# MF_badge_2021_rev_C.net
KiCad netlist of a schematic drawn in EAGLE
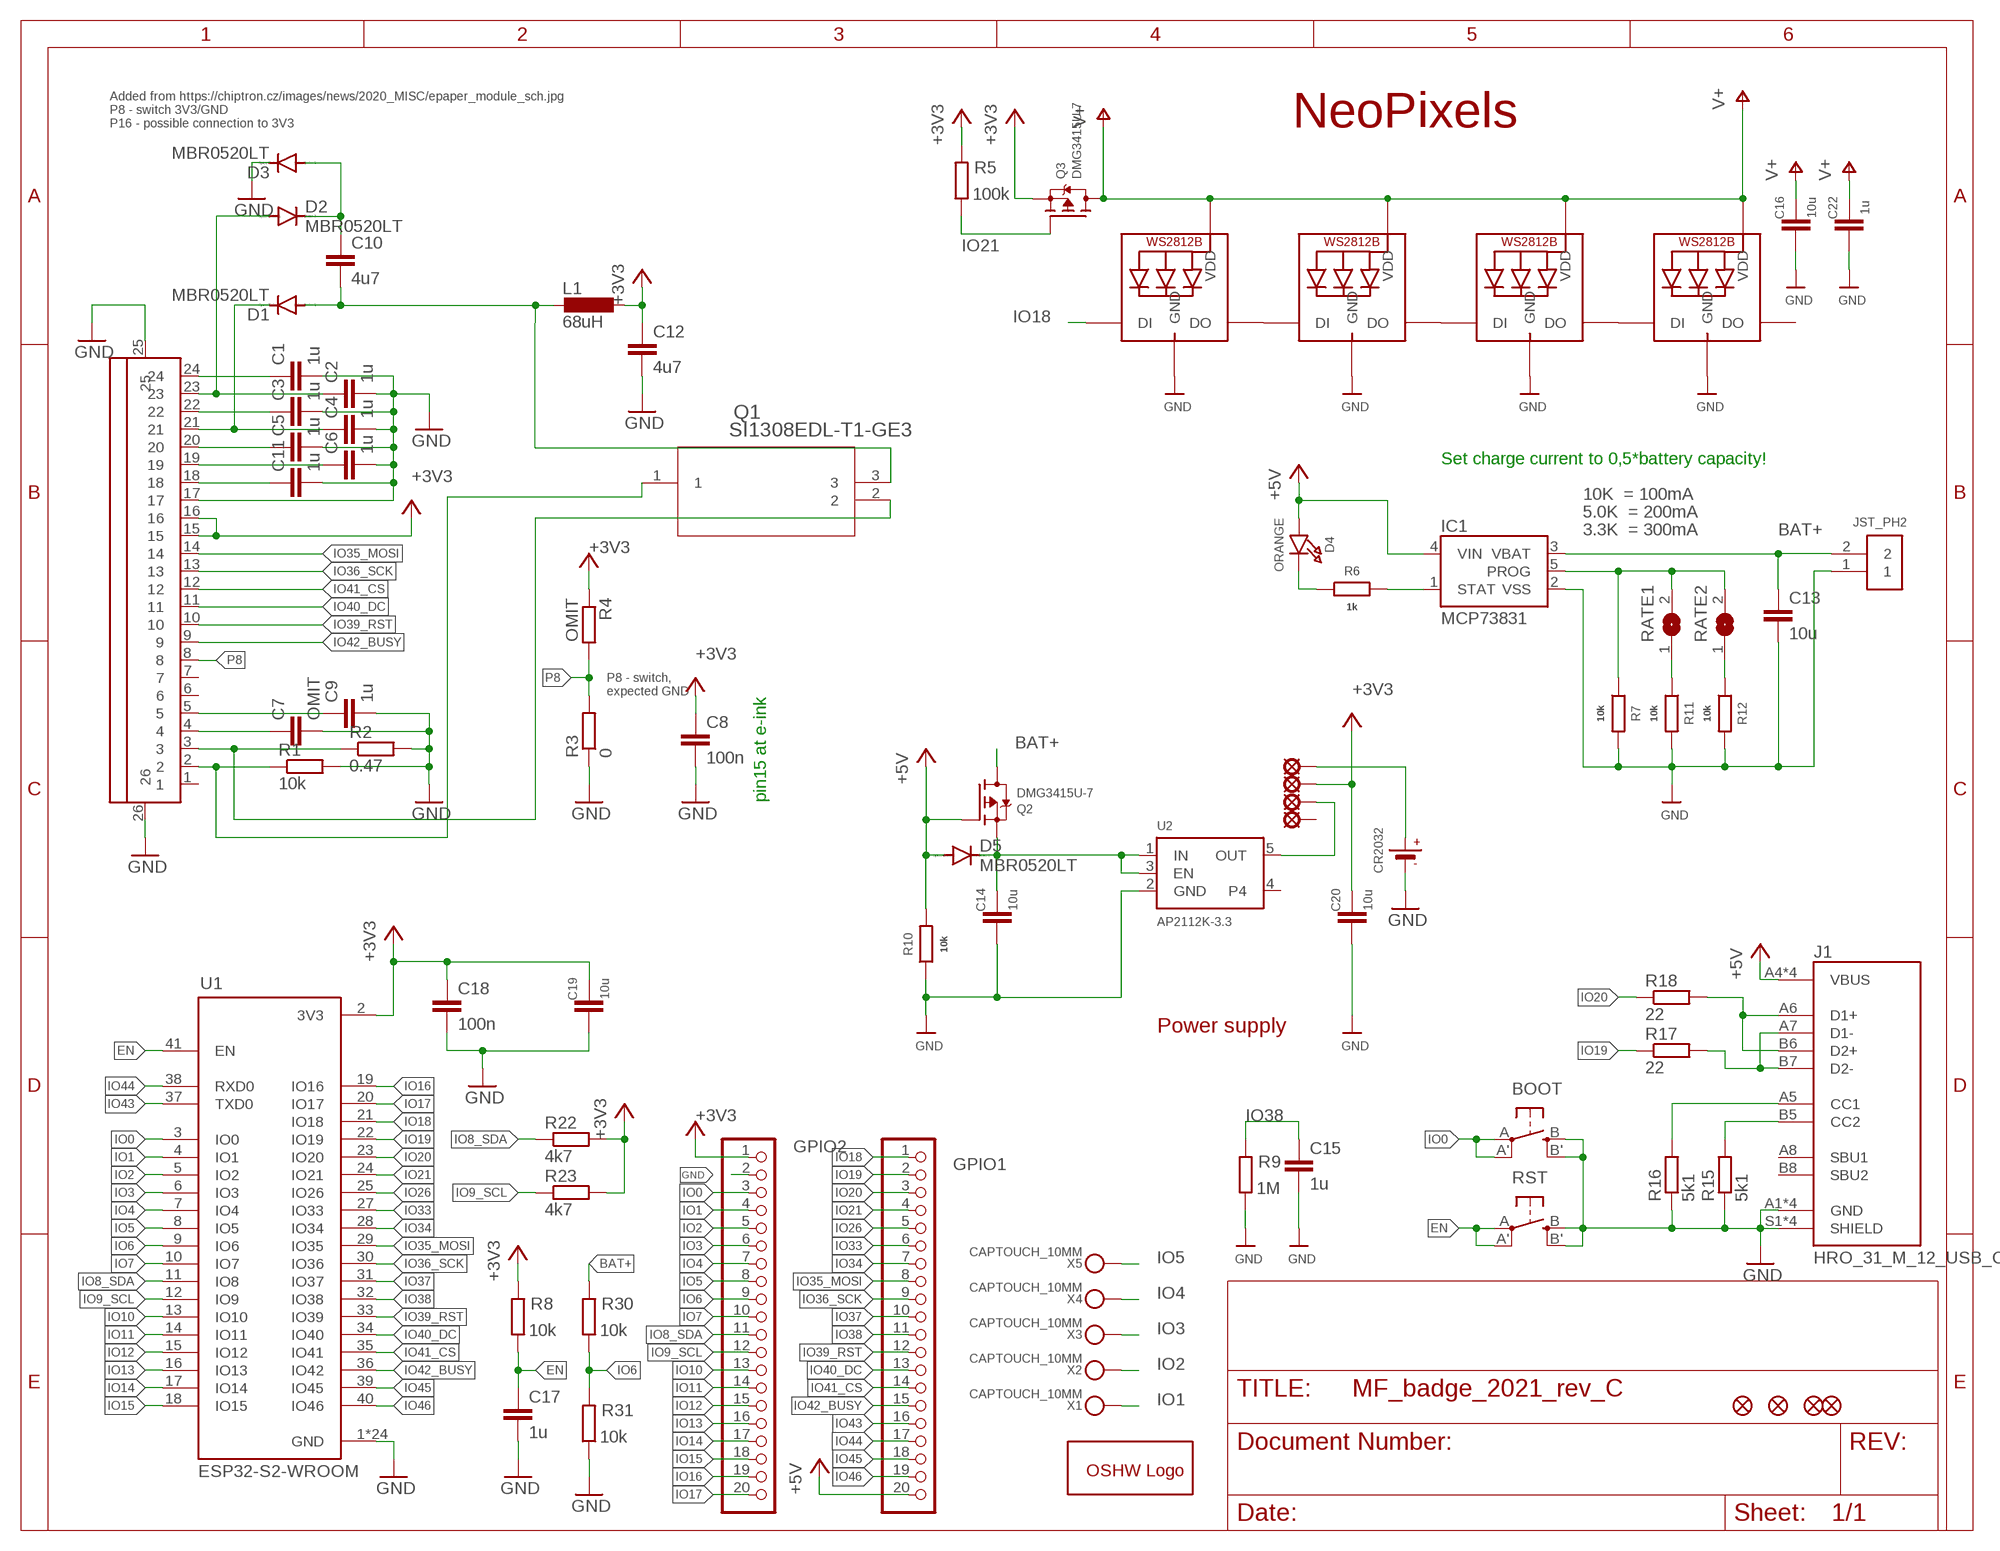
[diagram p0: schematic, sheet 1]

(export (version "E")
  (design (tool "Eeschema 10.0.6"))
  (components
    (comp (ref "BOOT")
      (value "BUTTON_KMR2_4.6X2.8")
      (footprint "eagle-import:BUTTON_KMR2_4.6X2.8")
      (libsource (lib "eagle-import") (part "BUTTON_KMR2_4.6X2.8"))
    )
    (comp (ref "C1")
      (value "1u")
      (footprint "eagle-import:C0805")
      (libsource (lib "eagle-import") (part "C-EUC0805"))
    )
    (comp (ref "C2")
      (value "1u")
      (footprint "eagle-import:C0805")
      (libsource (lib "eagle-import") (part "C-EUC0805"))
    )
    (comp (ref "C3")
      (value "1u")
      (footprint "eagle-import:C0805")
      (libsource (lib "eagle-import") (part "C-EUC0805"))
    )
    (comp (ref "C4")
      (value "1u")
      (footprint "eagle-import:C0805")
      (libsource (lib "eagle-import") (part "C-EUC0805"))
    )
    (comp (ref "C5")
      (value "1u")
      (footprint "eagle-import:C0805")
      (libsource (lib "eagle-import") (part "C-EUC0805"))
    )
    (comp (ref "C6")
      (value "1u")
      (footprint "eagle-import:C0805")
      (libsource (lib "eagle-import") (part "C-EUC0805"))
    )
    (comp (ref "C7")
      (value "OMIT")
      (footprint "eagle-import:C0805")
      (libsource (lib "eagle-import") (part "C-EUC0805"))
    )
    (comp (ref "C8")
      (value "100n")
      (footprint "eagle-import:C0805")
      (libsource (lib "eagle-import") (part "C-EUC0805"))
    )
    (comp (ref "C9")
      (value "1u")
      (footprint "eagle-import:C0805")
      (libsource (lib "eagle-import") (part "C-EUC0805"))
    )
    (comp (ref "C10")
      (value "4u7")
      (footprint "eagle-import:C0805")
      (libsource (lib "eagle-import") (part "C-EUC0805"))
    )
    (comp (ref "C11")
      (value "1u")
      (footprint "eagle-import:C0805")
      (libsource (lib "eagle-import") (part "C-EUC0805"))
    )
    (comp (ref "C12")
      (value "4u7")
      (footprint "eagle-import:C0805")
      (libsource (lib "eagle-import") (part "C-EUC0805"))
    )
    (comp (ref "C13")
      (value "10u")
      (footprint "eagle-import:C0805")
      (libsource (lib "eagle-import") (part "C-EUC0805"))
    )
    (comp (ref "C14")
      (value "10u")
      (footprint "eagle-import:C0805")
      (libsource (lib "eagle-import") (part "C-EUC0805"))
    )
    (comp (ref "C15")
      (value "1u")
      (footprint "eagle-import:C0805")
      (libsource (lib "eagle-import") (part "C-EUC0805"))
    )
    (comp (ref "C16")
      (value "10u")
      (footprint "eagle-import:C0805")
      (libsource (lib "eagle-import") (part "C-EUC0805"))
    )
    (comp (ref "C17")
      (value "1u")
      (footprint "eagle-import:C0805")
      (libsource (lib "eagle-import") (part "C-EUC0805"))
    )
    (comp (ref "C18")
      (value "100n")
      (footprint "eagle-import:C0805")
      (libsource (lib "eagle-import") (part "C-EUC0805"))
    )
    (comp (ref "C19")
      (value "10u")
      (footprint "eagle-import:C0805")
      (libsource (lib "eagle-import") (part "C-EUC0805"))
    )
    (comp (ref "C20")
      (value "10u")
      (footprint "eagle-import:C0805")
      (libsource (lib "eagle-import") (part "C-EUC0805"))
    )
    (comp (ref "C22")
      (value "1u")
      (footprint "eagle-import:C0805")
      (libsource (lib "eagle-import") (part "C-EUC0805"))
    )
    (comp (ref "CR2032")
      (value "BATTERYCR2032_BAT-HLD-001")
      (footprint "eagle-import:CR2032_SMT_BAT-HLD-001")
      (libsource (lib "eagle-import") (part "BATTERYCR2032_BAT-HLD-001"))
    )
    (comp (ref "D1")
      (value "MBR0520LT")
      (footprint "eagle-import:SOD123")
      (libsource (lib "eagle-import") (part "MBR0520LT"))
    )
    (comp (ref "D2")
      (value "MBR0520LT")
      (footprint "eagle-import:SOD123")
      (libsource (lib "eagle-import") (part "MBR0520LT"))
    )
    (comp (ref "D3")
      (value "MBR0520LT")
      (footprint "eagle-import:SOD123")
      (libsource (lib "eagle-import") (part "MBR0520LT"))
    )
    (comp (ref "D4")
      (value "ORANGE")
      (footprint "eagle-import:CHIPLED_0805_NOOUTLINE")
      (libsource (lib "eagle-import") (part "LED0805_NOOUTLINE"))
    )
    (comp (ref "D5")
      (value "MBR0520LT")
      (footprint "eagle-import:SOD123")
      (libsource (lib "eagle-import") (part "MBR0520LT"))
    )
    (comp (ref "FID1")
      (value "FIDUCIAL_1MM")
      (footprint "eagle-import:FIDUCIAL_1MM")
      (libsource (lib "eagle-import") (part "FIDUCIAL_1MM"))
    )
    (comp (ref "FID2")
      (value "FIDUCIAL_1MM")
      (footprint "eagle-import:FIDUCIAL_1MM")
      (libsource (lib "eagle-import") (part "FIDUCIAL_1MM"))
    )
    (comp (ref "FID3")
      (value "FIDUCIAL_1MM")
      (footprint "eagle-import:FIDUCIAL_1MM")
      (libsource (lib "eagle-import") (part "FIDUCIAL_1MM"))
    )
    (comp (ref "FID4")
      (value "FIDUCIAL_1MM")
      (footprint "eagle-import:FIDUCIAL_1MM")
      (libsource (lib "eagle-import") (part "FIDUCIAL_1MM"))
    )
    (comp (ref "GOLD_ORB_SM1")
      (value "OSHWLOGO_")
      (footprint "eagle-import:OSHW_5MM_LOGO")
      (libsource (lib "eagle-import") (part "OSHWLOGO_"))
    )
    (comp (ref "GPIO1")
      (value "PINHD-1X20")
      (footprint "eagle-import:1X20")
      (libsource (lib "eagle-import") (part "PINHD-1X20"))
    )
    (comp (ref "GPIO2")
      (value "PINHD-1X20")
      (footprint "eagle-import:1X20")
      (libsource (lib "eagle-import") (part "PINHD-1X20"))
    )
    (comp (ref "IC1")
      (value "MCP73831")
      (footprint "eagle-import:SOT95P290X120-5")
      (libsource (lib "eagle-import") (part "MCP73831"))
    )
    (comp (ref "J1")
      (value "HRO_31_M_12_USB_C")
      (footprint "eagle-import:HRO_31_M_12_USB_C")
      (libsource (lib "eagle-import") (part "HRO_31_M_12_USB_C"))
    )
    (comp (ref "L1")
      (value "68uH")
      (footprint "eagle-import:L4532P")
      (libsource (lib "eagle-import") (part "L-EUL4532P"))
    )
    (comp (ref "LED2")
      (value "WS2812B5050")
      (footprint "eagle-import:WS2812B")
      (libsource (lib "eagle-import") (part "WS2812B5050"))
    )
    (comp (ref "LED3")
      (value "WS2812B5050")
      (footprint "eagle-import:WS2812B")
      (libsource (lib "eagle-import") (part "WS2812B5050"))
    )
    (comp (ref "LED4")
      (value "WS2812B5050")
      (footprint "eagle-import:WS2812B")
      (libsource (lib "eagle-import") (part "WS2812B5050"))
    )
    (comp (ref "LED5")
      (value "WS2812B5050")
      (footprint "eagle-import:WS2812B")
      (libsource (lib "eagle-import") (part "WS2812B5050"))
    )
    (comp (ref "LSP1")
      (value "MCS10B")
      (footprint "eagle-import:MCS10B")
      (libsource (lib "eagle-import") (part "MCS10B"))
    )
    (comp (ref "LSP2")
      (value "MCS10B")
      (footprint "eagle-import:MCS10B")
      (libsource (lib "eagle-import") (part "MCS10B"))
    )
    (comp (ref "LSP3")
      (value "MCS10B")
      (footprint "eagle-import:MCS10B")
      (libsource (lib "eagle-import") (part "MCS10B"))
    )
    (comp (ref "LSP4")
      (value "MCS10B")
      (footprint "eagle-import:MCS10B")
      (libsource (lib "eagle-import") (part "MCS10B"))
    )
    (comp (ref "Q1")
      (value "SI1308EDL-T1-GE3")
      (footprint "eagle-import:MOSFET_8EDL-T1-GE3_VIS")
      (fields (field (name "COPYRIGHT") "Copyright (C) 2022 Ultra Librarian. All rights reserved."))
      (libsource (lib "eagle-import") (part "SI1308EDL-T1-GE3"))
    )
    (comp (ref "Q2")
      (value "DMG3415U-7")
      (footprint "eagle-import:SOT23-R")
      (libsource (lib "eagle-import") (part "MOSFET-P"))
    )
    (comp (ref "Q3")
      (value "DMG3415U-7")
      (footprint "eagle-import:SOT23-R")
      (libsource (lib "eagle-import") (part "MOSFET-P"))
    )
    (comp (ref "R1")
      (value "10k")
      (footprint "eagle-import:R0805")
      (libsource (lib "eagle-import") (part "R-EU_R0805"))
    )
    (comp (ref "R2")
      (value "0.47")
      (footprint "eagle-import:R0805")
      (libsource (lib "eagle-import") (part "R-EU_R0805"))
    )
    (comp (ref "R3")
      (value "0")
      (footprint "eagle-import:R0805")
      (libsource (lib "eagle-import") (part "R-EU_R0805"))
    )
    (comp (ref "R4")
      (value "OMIT")
      (footprint "eagle-import:R0805")
      (libsource (lib "eagle-import") (part "R-EU_R0805"))
    )
    (comp (ref "R5")
      (value "100k")
      (footprint "eagle-import:R0805")
      (libsource (lib "eagle-import") (part "R-EU_R0805"))
    )
    (comp (ref "R6")
      (value "1k")
      (footprint "eagle-import:R0805")
      (libsource (lib "eagle-import") (part "R-EU_R0805"))
    )
    (comp (ref "R7")
      (value "10k")
      (footprint "eagle-import:R0805")
      (libsource (lib "eagle-import") (part "R-EU_R0805"))
    )
    (comp (ref "R8")
      (value "10k")
      (footprint "eagle-import:R0805")
      (libsource (lib "eagle-import") (part "R-EU_R0805"))
    )
    (comp (ref "R9")
      (value "1M")
      (footprint "eagle-import:R0805")
      (libsource (lib "eagle-import") (part "R-EU_R0805"))
    )
    (comp (ref "R10")
      (value "10k")
      (footprint "eagle-import:R0805")
      (libsource (lib "eagle-import") (part "R-EU_R0805"))
    )
    (comp (ref "R11")
      (value "10k")
      (footprint "eagle-import:R0805")
      (libsource (lib "eagle-import") (part "R-EU_R0805"))
    )
    (comp (ref "R12")
      (value "10k")
      (footprint "eagle-import:R0805")
      (libsource (lib "eagle-import") (part "R-EU_R0805"))
    )
    (comp (ref "R15")
      (value "5k1")
      (footprint "eagle-import:R0805")
      (libsource (lib "eagle-import") (part "R-EU_R0805"))
    )
    (comp (ref "R16")
      (value "5k1")
      (footprint "eagle-import:R0805")
      (libsource (lib "eagle-import") (part "R-EU_R0805"))
    )
    (comp (ref "R17")
      (value "22")
      (footprint "eagle-import:R0805")
      (libsource (lib "eagle-import") (part "R-EU_R0805"))
    )
    (comp (ref "R18")
      (value "22")
      (footprint "eagle-import:R0805")
      (libsource (lib "eagle-import") (part "R-EU_R0805"))
    )
    (comp (ref "R22")
      (value "4k7")
      (footprint "eagle-import:R0805")
      (libsource (lib "eagle-import") (part "R-EU_R0805"))
    )
    (comp (ref "R23")
      (value "4k7")
      (footprint "eagle-import:R0805")
      (libsource (lib "eagle-import") (part "R-EU_R0805"))
    )
    (comp (ref "R30")
      (value "10k")
      (footprint "eagle-import:R0805")
      (libsource (lib "eagle-import") (part "R-EU_R0805"))
    )
    (comp (ref "R31")
      (value "10k")
      (footprint "eagle-import:R0805")
      (libsource (lib "eagle-import") (part "R-EU_R0805"))
    )
    (comp (ref "RATE1")
      (value "SOLDERJUMPER")
      (footprint "eagle-import:SOLDERJUMPER_ARROW_NOPASTE")
      (libsource (lib "eagle-import") (part "SOLDERJUMPER"))
    )
    (comp (ref "RATE2")
      (value "SOLDERJUMPER")
      (footprint "eagle-import:SOLDERJUMPER_ARROW_NOPASTE")
      (libsource (lib "eagle-import") (part "SOLDERJUMPER"))
    )
    (comp (ref "RST")
      (value "BUTTON_KMR2_4.6X2.8")
      (footprint "eagle-import:BUTTON_KMR2_4.6X2.8")
      (libsource (lib "eagle-import") (part "BUTTON_KMR2_4.6X2.8"))
    )
    (comp (ref "U$1")
      (value "2.13_EINK")
      (footprint "eagle-import:2.13_EINK")
      (libsource (lib "eagle-import") (part "2.13_EINK"))
    )
    (comp (ref "U$8")
      (value "JST_PH2")
      (footprint "eagle-import:JSTPH2")
      (libsource (lib "eagle-import") (part "JST_PH2"))
    )
    (comp (ref "U1")
      (value "ESP32-S2-WROOM")
      (footprint "eagle-import:XCVR_ESP32-S2-WROOM")
      (fields (field (name "MF") "Espressif Systems"))
      (libsource (lib "eagle-import") (part "ESP32-S2-WROOM"))
    )
    (comp (ref "U2")
      (value "AP2112K-3.3")
      (footprint "eagle-import:SOT23-5")
      (libsource (lib "eagle-import") (part "VREG_SOT23-5"))
    )
    (comp (ref "X1")
      (value "CAPTOUCH_10MM")
      (footprint "eagle-import:CAPTOUCH_6X9MM")
      (libsource (lib "eagle-import") (part "CAPTOUCH_MONOPAD_6X9"))
    )
    (comp (ref "X2")
      (value "CAPTOUCH_10MM")
      (footprint "eagle-import:CAPTOUCH_6X9MM")
      (libsource (lib "eagle-import") (part "CAPTOUCH_MONOPAD_6X9"))
    )
    (comp (ref "X3")
      (value "CAPTOUCH_10MM")
      (footprint "eagle-import:CAPTOUCH_6X9MM")
      (libsource (lib "eagle-import") (part "CAPTOUCH_MONOPAD_6X9"))
    )
    (comp (ref "X4")
      (value "CAPTOUCH_10MM")
      (footprint "eagle-import:CAPTOUCH_6X9MM")
      (libsource (lib "eagle-import") (part "CAPTOUCH_MONOPAD_6X9"))
    )
    (comp (ref "X5")
      (value "CAPTOUCH_10MM")
      (footprint "eagle-import:CAPTOUCH_6X9MM")
      (libsource (lib "eagle-import") (part "CAPTOUCH_MONOPAD_6X9"))
    )
  )
  (nets
    (net (code "1") (name "+3V3") (class "Default")
      (node (ref "C12") (pin "1") (pinfunction "1_1") (pintype "passive"))
      (node (ref "C18") (pin "1") (pinfunction "1_1") (pintype "passive"))
      (node (ref "C19") (pin "1") (pinfunction "1_1") (pintype "passive"))
      (node (ref "C20") (pin "1") (pinfunction "1_1") (pintype "passive"))
      (node (ref "C8") (pin "1") (pinfunction "1_1") (pintype "passive"))
      (node (ref "GPIO2") (pin "1") (pinfunction "1_1") (pintype "passive"))
      (node (ref "L1") (pin "1") (pinfunction "1_1") (pintype "passive"))
      (node (ref "LSP2") (pin "MP") (pinfunction "MP_MP") (pintype "passive"))
      (node (ref "Q3") (pin "2") (pinfunction "S_2") (pintype "passive"))
      (node (ref "R22") (pin "2") (pinfunction "2_2") (pintype "passive"))
      (node (ref "R23") (pin "2") (pinfunction "2_2") (pintype "passive"))
      (node (ref "R4") (pin "1") (pinfunction "1_1") (pintype "passive"))
      (node (ref "R5") (pin "2") (pinfunction "2_2") (pintype "passive"))
      (node (ref "R8") (pin "2") (pinfunction "2_2") (pintype "passive"))
      (node (ref "U$1") (pin "15") (pinfunction "15_15") (pintype "bidirectional"))
      (node (ref "U$1") (pin "16") (pinfunction "16_16") (pintype "bidirectional"))
      (node (ref "U1") (pin "2") (pinfunction "3V3_2") (pintype "power_in"))
    )
    (net (code "2") (name "+5V") (class "Default")
      (node (ref "D4") (pin "A") (pinfunction "A_A") (pintype "passive"))
      (node (ref "D5") (pin "A") (pinfunction "A_A") (pintype "passive"))
      (node (ref "GPIO1") (pin "20") (pinfunction "20_20") (pintype "passive"))
      (node (ref "IC1") (pin "4") (pinfunction "VIN_4") (pintype "power_in"))
      (node (ref "J1") (pin "A4") (pinfunction "VBUS_A4") (pintype "passive"))
      (node (ref "J1") (pin "A9") (pinfunction "VBUS_A9") (pintype "passive"))
      (node (ref "J1") (pin "B4") (pinfunction "VBUS_B4") (pintype "passive"))
      (node (ref "J1") (pin "B9") (pinfunction "VBUS_B9") (pintype "passive"))
      (node (ref "Q2") (pin "1") (pinfunction "G_1") (pintype "passive"))
      (node (ref "R10") (pin "2") (pinfunction "2_2") (pintype "passive"))
    )
    (net (code "3") (name "BAT+") (class "Default")
      (node (ref "C13") (pin "1") (pinfunction "1_1") (pintype "passive"))
      (node (ref "IC1") (pin "3") (pinfunction "VBAT_3") (pintype "power_in"))
      (node (ref "Q2") (pin "3") (pinfunction "D_3") (pintype "passive"))
      (node (ref "R30") (pin "2") (pinfunction "2_2") (pintype "passive"))
      (node (ref "U$8") (pin "2") (pinfunction "2_2") (pintype "bidirectional"))
    )
    (net (code "4") (name "EN") (class "Default")
      (node (ref "C17") (pin "1") (pinfunction "1_1") (pintype "passive"))
      (node (ref "R8") (pin "1") (pinfunction "1_1") (pintype "passive"))
      (node (ref "RST") (pin "A") (pinfunction "P_A") (pintype "passive"))
      (node (ref "RST") (pin "A'") (pinfunction "P1_A'") (pintype "passive"))
      (node (ref "U1") (pin "41") (pinfunction "EN_41") (pintype "input"))
    )
    (net (code "5") (name "GND") (class "Default")
      (node (ref "BOOT") (pin "B") (pinfunction "S_B") (pintype "passive"))
      (node (ref "BOOT") (pin "B'") (pinfunction "S1_B'") (pintype "passive"))
      (node (ref "C1") (pin "2") (pinfunction "2_2") (pintype "passive"))
      (node (ref "C11") (pin "2") (pinfunction "2_2") (pintype "passive"))
      (node (ref "C12") (pin "2") (pinfunction "2_2") (pintype "passive"))
      (node (ref "C13") (pin "2") (pinfunction "2_2") (pintype "passive"))
      (node (ref "C14") (pin "2") (pinfunction "2_2") (pintype "passive"))
      (node (ref "C15") (pin "2") (pinfunction "2_2") (pintype "passive"))
      (node (ref "C16") (pin "2") (pinfunction "2_2") (pintype "passive"))
      (node (ref "C17") (pin "2") (pinfunction "2_2") (pintype "passive"))
      (node (ref "C18") (pin "2") (pinfunction "2_2") (pintype "passive"))
      (node (ref "C19") (pin "2") (pinfunction "2_2") (pintype "passive"))
      (node (ref "C2") (pin "2") (pinfunction "2_2") (pintype "passive"))
      (node (ref "C20") (pin "2") (pinfunction "2_2") (pintype "passive"))
      (node (ref "C22") (pin "2") (pinfunction "2_2") (pintype "passive"))
      (node (ref "C3") (pin "2") (pinfunction "2_2") (pintype "passive"))
      (node (ref "C4") (pin "2") (pinfunction "2_2") (pintype "passive"))
      (node (ref "C5") (pin "2") (pinfunction "2_2") (pintype "passive"))
      (node (ref "C6") (pin "2") (pinfunction "2_2") (pintype "passive"))
      (node (ref "C7") (pin "2") (pinfunction "2_2") (pintype "passive"))
      (node (ref "C8") (pin "2") (pinfunction "2_2") (pintype "passive"))
      (node (ref "C9") (pin "2") (pinfunction "2_2") (pintype "passive"))
      (node (ref "CR2032") (pin "-") (pinfunction "-_-") (pintype "passive"))
      (node (ref "D3") (pin "C") (pinfunction "C_C") (pintype "passive"))
      (node (ref "GPIO2") (pin "2") (pinfunction "2_2") (pintype "passive"))
      (node (ref "IC1") (pin "2") (pinfunction "VSS_2") (pintype "power_in"))
      (node (ref "J1") (pin "A1") (pinfunction "GND_A1") (pintype "passive"))
      (node (ref "J1") (pin "A12") (pinfunction "GND_A12") (pintype "passive"))
      (node (ref "J1") (pin "B1") (pinfunction "GND_B1") (pintype "passive"))
      (node (ref "J1") (pin "B12") (pinfunction "GND_B12") (pintype "passive"))
      (node (ref "J1") (pin "S1") (pinfunction "SHIELD_S1") (pintype "passive"))
      (node (ref "J1") (pin "S2") (pinfunction "SHIELD_S2") (pintype "passive"))
      (node (ref "J1") (pin "S3") (pinfunction "SHIELD_S3") (pintype "passive"))
      (node (ref "J1") (pin "S4") (pinfunction "SHIELD_S4") (pintype "passive"))
      (node (ref "LED2") (pin "3-GND") (pinfunction "GND_3-GND") (pintype "power_in"))
      (node (ref "LED3") (pin "3-GND") (pinfunction "GND_3-GND") (pintype "power_in"))
      (node (ref "LED4") (pin "3-GND") (pinfunction "GND_3-GND") (pintype "power_in"))
      (node (ref "LED5") (pin "3-GND") (pinfunction "GND_3-GND") (pintype "power_in"))
      (node (ref "R1") (pin "2") (pinfunction "2_2") (pintype "passive"))
      (node (ref "R10") (pin "1") (pinfunction "1_1") (pintype "passive"))
      (node (ref "R11") (pin "2") (pinfunction "2_2") (pintype "passive"))
      (node (ref "R12") (pin "2") (pinfunction "2_2") (pintype "passive"))
      (node (ref "R15") (pin "1") (pinfunction "1_1") (pintype "passive"))
      (node (ref "R16") (pin "1") (pinfunction "1_1") (pintype "passive"))
      (node (ref "R2") (pin "2") (pinfunction "2_2") (pintype "passive"))
      (node (ref "R3") (pin "1") (pinfunction "1_1") (pintype "passive"))
      (node (ref "R31") (pin "1") (pinfunction "1_1") (pintype "passive"))
      (node (ref "R7") (pin "2") (pinfunction "2_2") (pintype "passive"))
      (node (ref "R9") (pin "1") (pinfunction "1_1") (pintype "passive"))
      (node (ref "RST") (pin "B") (pinfunction "S_B") (pintype "passive"))
      (node (ref "RST") (pin "B'") (pinfunction "S1_B'") (pintype "passive"))
      (node (ref "U$1") (pin "17") (pinfunction "17_17") (pintype "bidirectional"))
      (node (ref "U$1") (pin "25") (pinfunction "25_25") (pintype "power_in"))
      (node (ref "U$1") (pin "26") (pinfunction "26_26") (pintype "power_in"))
      (node (ref "U$8") (pin "1") (pinfunction "1_1") (pintype "bidirectional"))
      (node (ref "U1") (pin "1") (pinfunction "GND_1") (pintype "power_in"))
      (node (ref "U1") (pin "26") (pinfunction "GND_26") (pintype "power_in"))
      (node (ref "U1") (pin "42") (pinfunction "GND_42") (pintype "power_in"))
      (node (ref "U1") (pin "43.1") (pinfunction "GND_43.1") (pintype "power_in"))
      (node (ref "U1") (pin "43.10") (pinfunction "GND_43.10") (pintype "power_in"))
      (node (ref "U1") (pin "43.11") (pinfunction "GND_43.11") (pintype "power_in"))
      (node (ref "U1") (pin "43.12") (pinfunction "GND_43.12") (pintype "power_in"))
      (node (ref "U1") (pin "43.13") (pinfunction "GND_43.13") (pintype "power_in"))
      (node (ref "U1") (pin "43.14") (pinfunction "GND_43.14") (pintype "power_in"))
      (node (ref "U1") (pin "43.15") (pinfunction "GND_43.15") (pintype "power_in"))
      (node (ref "U1") (pin "43.16") (pinfunction "GND_43.16") (pintype "power_in"))
      (node (ref "U1") (pin "43.17") (pinfunction "GND_43.17") (pintype "power_in"))
      (node (ref "U1") (pin "43.18") (pinfunction "GND_43.18") (pintype "power_in"))
      (node (ref "U1") (pin "43.19") (pinfunction "GND_43.19") (pintype "power_in"))
      (node (ref "U1") (pin "43.2") (pinfunction "GND_43.2") (pintype "power_in"))
      (node (ref "U1") (pin "43.20") (pinfunction "GND_43.20") (pintype "power_in"))
      (node (ref "U1") (pin "43.21") (pinfunction "GND_43.21") (pintype "power_in"))
      (node (ref "U1") (pin "43.3") (pinfunction "GND_43.3") (pintype "power_in"))
      (node (ref "U1") (pin "43.4") (pinfunction "GND_43.4") (pintype "power_in"))
      (node (ref "U1") (pin "43.5") (pinfunction "GND_43.5") (pintype "power_in"))
      (node (ref "U1") (pin "43.6") (pinfunction "GND_43.6") (pintype "power_in"))
      (node (ref "U1") (pin "43.7") (pinfunction "GND_43.7") (pintype "power_in"))
      (node (ref "U1") (pin "43.8") (pinfunction "GND_43.8") (pintype "power_in"))
      (node (ref "U1") (pin "43.9") (pinfunction "GND_43.9") (pintype "power_in"))
      (node (ref "U2") (pin "2") (pinfunction "GND_2") (pintype "power_in"))
    )
    (net (code "6") (name "IO0") (class "Default")
      (node (ref "BOOT") (pin "A") (pinfunction "P_A") (pintype "passive"))
      (node (ref "BOOT") (pin "A'") (pinfunction "P1_A'") (pintype "passive"))
      (node (ref "GPIO2") (pin "3") (pinfunction "3_3") (pintype "passive"))
      (node (ref "U1") (pin "3") (pinfunction "IO0_3") (pintype "bidirectional"))
    )
    (net (code "7") (name "IO1") (class "Default")
      (node (ref "GPIO2") (pin "4") (pinfunction "4_4") (pintype "passive"))
      (node (ref "U1") (pin "4") (pinfunction "IO1_4") (pintype "bidirectional"))
      (node (ref "X1") (pin "P$1") (pinfunction "P$1_P$1") (pintype "bidirectional"))
    )
    (net (code "8") (name "IO2") (class "Default")
      (node (ref "GPIO2") (pin "5") (pinfunction "5_5") (pintype "passive"))
      (node (ref "U1") (pin "5") (pinfunction "IO2_5") (pintype "bidirectional"))
      (node (ref "X2") (pin "P$1") (pinfunction "P$1_P$1") (pintype "bidirectional"))
    )
    (net (code "9") (name "IO3") (class "Default")
      (node (ref "GPIO2") (pin "6") (pinfunction "6_6") (pintype "passive"))
      (node (ref "U1") (pin "6") (pinfunction "IO3_6") (pintype "bidirectional"))
      (node (ref "X3") (pin "P$1") (pinfunction "P$1_P$1") (pintype "bidirectional"))
    )
    (net (code "10") (name "IO4") (class "Default")
      (node (ref "GPIO2") (pin "7") (pinfunction "7_7") (pintype "passive"))
      (node (ref "U1") (pin "7") (pinfunction "IO4_7") (pintype "bidirectional"))
      (node (ref "X4") (pin "P$1") (pinfunction "P$1_P$1") (pintype "bidirectional"))
    )
    (net (code "11") (name "IO5") (class "Default")
      (node (ref "GPIO2") (pin "8") (pinfunction "8_8") (pintype "passive"))
      (node (ref "U1") (pin "8") (pinfunction "IO5_8") (pintype "bidirectional"))
      (node (ref "X5") (pin "P$1") (pinfunction "P$1_P$1") (pintype "bidirectional"))
    )
    (net (code "12") (name "IO6") (class "Default")
      (node (ref "GPIO2") (pin "9") (pinfunction "9_9") (pintype "passive"))
      (node (ref "R30") (pin "1") (pinfunction "1_1") (pintype "passive"))
      (node (ref "R31") (pin "2") (pinfunction "2_2") (pintype "passive"))
      (node (ref "U1") (pin "9") (pinfunction "IO6_9") (pintype "bidirectional"))
    )
    (net (code "13") (name "IO7") (class "Default")
      (node (ref "GPIO2") (pin "10") (pinfunction "10_10") (pintype "passive"))
      (node (ref "U1") (pin "10") (pinfunction "IO7_10") (pintype "bidirectional"))
    )
    (net (code "14") (name "IO8_SDA") (class "Default")
      (node (ref "GPIO2") (pin "11") (pinfunction "11_11") (pintype "passive"))
      (node (ref "R22") (pin "1") (pinfunction "1_1") (pintype "passive"))
      (node (ref "U1") (pin "11") (pinfunction "IO8_11") (pintype "bidirectional"))
    )
    (net (code "15") (name "IO9_SCL") (class "Default")
      (node (ref "GPIO2") (pin "12") (pinfunction "12_12") (pintype "passive"))
      (node (ref "R23") (pin "1") (pinfunction "1_1") (pintype "passive"))
      (node (ref "U1") (pin "12") (pinfunction "IO9_12") (pintype "bidirectional"))
    )
    (net (code "16") (name "IO10") (class "Default")
      (node (ref "GPIO2") (pin "13") (pinfunction "13_13") (pintype "passive"))
      (node (ref "U1") (pin "13") (pinfunction "IO10_13") (pintype "bidirectional"))
    )
    (net (code "17") (name "IO11") (class "Default")
      (node (ref "GPIO2") (pin "14") (pinfunction "14_14") (pintype "passive"))
      (node (ref "U1") (pin "14") (pinfunction "IO11_14") (pintype "bidirectional"))
    )
    (net (code "18") (name "IO12") (class "Default")
      (node (ref "GPIO2") (pin "15") (pinfunction "15_15") (pintype "passive"))
      (node (ref "U1") (pin "15") (pinfunction "IO12_15") (pintype "bidirectional"))
    )
    (net (code "19") (name "IO13") (class "Default")
      (node (ref "GPIO2") (pin "16") (pinfunction "16_16") (pintype "passive"))
      (node (ref "U1") (pin "16") (pinfunction "IO13_16") (pintype "bidirectional"))
    )
    (net (code "20") (name "IO14") (class "Default")
      (node (ref "GPIO2") (pin "17") (pinfunction "17_17") (pintype "passive"))
      (node (ref "U1") (pin "17") (pinfunction "IO14_17") (pintype "bidirectional"))
    )
    (net (code "21") (name "IO15") (class "Default")
      (node (ref "GPIO2") (pin "18") (pinfunction "18_18") (pintype "passive"))
      (node (ref "U1") (pin "18") (pinfunction "IO15_18") (pintype "bidirectional"))
    )
    (net (code "22") (name "IO16") (class "Default")
      (node (ref "GPIO2") (pin "19") (pinfunction "19_19") (pintype "passive"))
      (node (ref "U1") (pin "19") (pinfunction "IO16_19") (pintype "bidirectional"))
    )
    (net (code "23") (name "IO17") (class "Default")
      (node (ref "GPIO2") (pin "20") (pinfunction "20_20") (pintype "passive"))
      (node (ref "U1") (pin "20") (pinfunction "IO17_20") (pintype "bidirectional"))
    )
    (net (code "24") (name "IO18") (class "Default")
      (node (ref "GPIO1") (pin "1") (pinfunction "1_1") (pintype "passive"))
      (node (ref "LED2") (pin "4-DIN") (pinfunction "DI_4-DIN") (pintype "input"))
      (node (ref "U1") (pin "21") (pinfunction "IO18_21") (pintype "bidirectional"))
    )
    (net (code "25") (name "IO19") (class "Default")
      (node (ref "GPIO1") (pin "2") (pinfunction "2_2") (pintype "passive"))
      (node (ref "R17") (pin "1") (pinfunction "1_1") (pintype "passive"))
      (node (ref "U1") (pin "22") (pinfunction "IO19_22") (pintype "bidirectional"))
    )
    (net (code "26") (name "IO20") (class "Default")
      (node (ref "GPIO1") (pin "3") (pinfunction "3_3") (pintype "passive"))
      (node (ref "R18") (pin "1") (pinfunction "1_1") (pintype "passive"))
      (node (ref "U1") (pin "23") (pinfunction "IO20_23") (pintype "bidirectional"))
    )
    (net (code "27") (name "IO21") (class "Default")
      (node (ref "GPIO1") (pin "4") (pinfunction "4_4") (pintype "passive"))
      (node (ref "Q3") (pin "1") (pinfunction "G_1") (pintype "passive"))
      (node (ref "R5") (pin "1") (pinfunction "1_1") (pintype "passive"))
      (node (ref "U1") (pin "24") (pinfunction "IO21_24") (pintype "bidirectional"))
    )
    (net (code "28") (name "IO26") (class "Default")
      (node (ref "GPIO1") (pin "5") (pinfunction "5_5") (pintype "passive"))
      (node (ref "U1") (pin "25") (pinfunction "IO26_25") (pintype "bidirectional"))
    )
    (net (code "29") (name "IO33") (class "Default")
      (node (ref "GPIO1") (pin "6") (pinfunction "6_6") (pintype "passive"))
      (node (ref "U1") (pin "27") (pinfunction "IO33_27") (pintype "bidirectional"))
    )
    (net (code "30") (name "IO34") (class "Default")
      (node (ref "GPIO1") (pin "7") (pinfunction "7_7") (pintype "passive"))
      (node (ref "U1") (pin "28") (pinfunction "IO34_28") (pintype "bidirectional"))
    )
    (net (code "31") (name "IO35_MOSI") (class "Default")
      (node (ref "GPIO1") (pin "8") (pinfunction "8_8") (pintype "passive"))
      (node (ref "U$1") (pin "14") (pinfunction "14_14") (pintype "bidirectional"))
      (node (ref "U1") (pin "29") (pinfunction "IO35_29") (pintype "bidirectional"))
    )
    (net (code "32") (name "IO36_SCK") (class "Default")
      (node (ref "GPIO1") (pin "9") (pinfunction "9_9") (pintype "passive"))
      (node (ref "U$1") (pin "13") (pinfunction "13_13") (pintype "bidirectional"))
      (node (ref "U1") (pin "30") (pinfunction "IO36_30") (pintype "bidirectional"))
    )
    (net (code "33") (name "IO37") (class "Default")
      (node (ref "GPIO1") (pin "10") (pinfunction "10_10") (pintype "passive"))
      (node (ref "U1") (pin "31") (pinfunction "IO37_31") (pintype "bidirectional"))
    )
    (net (code "34") (name "IO38") (class "Default")
      (node (ref "C15") (pin "1") (pinfunction "1_1") (pintype "passive"))
      (node (ref "GPIO1") (pin "11") (pinfunction "11_11") (pintype "passive"))
      (node (ref "R9") (pin "2") (pinfunction "2_2") (pintype "passive"))
      (node (ref "U1") (pin "32") (pinfunction "IO38_32") (pintype "bidirectional"))
    )
    (net (code "35") (name "IO39_RST") (class "Default")
      (node (ref "GPIO1") (pin "12") (pinfunction "12_12") (pintype "passive"))
      (node (ref "U$1") (pin "10") (pinfunction "10_10") (pintype "bidirectional"))
      (node (ref "U1") (pin "33") (pinfunction "IO39_33") (pintype "bidirectional"))
    )
    (net (code "36") (name "IO40_DC") (class "Default")
      (node (ref "GPIO1") (pin "13") (pinfunction "13_13") (pintype "passive"))
      (node (ref "U$1") (pin "11") (pinfunction "11_11") (pintype "bidirectional"))
      (node (ref "U1") (pin "34") (pinfunction "IO40_34") (pintype "bidirectional"))
    )
    (net (code "37") (name "IO41_CS") (class "Default")
      (node (ref "GPIO1") (pin "14") (pinfunction "14_14") (pintype "passive"))
      (node (ref "U$1") (pin "12") (pinfunction "12_12") (pintype "bidirectional"))
      (node (ref "U1") (pin "35") (pinfunction "IO41_35") (pintype "bidirectional"))
    )
    (net (code "38") (name "IO42_BUSY") (class "Default")
      (node (ref "GPIO1") (pin "15") (pinfunction "15_15") (pintype "passive"))
      (node (ref "U$1") (pin "9") (pinfunction "9_9") (pintype "bidirectional"))
      (node (ref "U1") (pin "36") (pinfunction "IO42_36") (pintype "bidirectional"))
    )
    (net (code "39") (name "IO43") (class "Default")
      (node (ref "GPIO1") (pin "16") (pinfunction "16_16") (pintype "passive"))
      (node (ref "U1") (pin "37") (pinfunction "TXD0_37") (pintype "bidirectional"))
    )
    (net (code "40") (name "IO44") (class "Default")
      (node (ref "GPIO1") (pin "17") (pinfunction "17_17") (pintype "passive"))
      (node (ref "U1") (pin "38") (pinfunction "RXD0_38") (pintype "bidirectional"))
    )
    (net (code "41") (name "IO45") (class "Default")
      (node (ref "GPIO1") (pin "18") (pinfunction "18_18") (pintype "passive"))
      (node (ref "U1") (pin "39") (pinfunction "IO45_39") (pintype "bidirectional"))
    )
    (net (code "42") (name "IO46") (class "Default")
      (node (ref "GPIO1") (pin "19") (pinfunction "19_19") (pintype "passive"))
      (node (ref "U1") (pin "40") (pinfunction "IO46_40") (pintype "bidirectional"))
    )
    (net (code "43") (name "Net-(C1-Pad1)") (class "Default")
      (node (ref "C1") (pin "1") (pinfunction "1_1") (pintype "passive"))
      (node (ref "U$1") (pin "24") (pinfunction "24_24") (pintype "bidirectional"))
    )
    (net (code "44") (name "Net-(C2-Pad1)") (class "Default")
      (node (ref "C2") (pin "1") (pinfunction "1_1") (pintype "passive"))
      (node (ref "D2") (pin "A") (pinfunction "A_A") (pintype "passive"))
      (node (ref "U$1") (pin "23") (pinfunction "23_23") (pintype "bidirectional"))
    )
    (net (code "45") (name "Net-(C3-Pad1)") (class "Default")
      (node (ref "C3") (pin "1") (pinfunction "1_1") (pintype "passive"))
      (node (ref "U$1") (pin "22") (pinfunction "22_22") (pintype "bidirectional"))
    )
    (net (code "46") (name "Net-(C4-Pad1)") (class "Default")
      (node (ref "C4") (pin "1") (pinfunction "1_1") (pintype "passive"))
      (node (ref "D1") (pin "C") (pinfunction "C_C") (pintype "passive"))
      (node (ref "U$1") (pin "21") (pinfunction "21_21") (pintype "bidirectional"))
    )
    (net (code "47") (name "Net-(C5-Pad1)") (class "Default")
      (node (ref "C5") (pin "1") (pinfunction "1_1") (pintype "passive"))
      (node (ref "U$1") (pin "20") (pinfunction "20_20") (pintype "bidirectional"))
    )
    (net (code "48") (name "Net-(C6-Pad1)") (class "Default")
      (node (ref "C6") (pin "1") (pinfunction "1_1") (pintype "passive"))
      (node (ref "U$1") (pin "19") (pinfunction "19_19") (pintype "bidirectional"))
    )
    (net (code "49") (name "Net-(C7-Pad1)") (class "Default")
      (node (ref "C7") (pin "1") (pinfunction "1_1") (pintype "passive"))
      (node (ref "U$1") (pin "4") (pinfunction "4_4") (pintype "bidirectional"))
    )
    (net (code "50") (name "Net-(C9-Pad1)") (class "Default")
      (node (ref "C9") (pin "1") (pinfunction "1_1") (pintype "passive"))
      (node (ref "U$1") (pin "5") (pinfunction "5_5") (pintype "bidirectional"))
    )
    (net (code "51") (name "Net-(C10-Pad1)") (class "Default")
      (node (ref "C10") (pin "1") (pinfunction "1_1") (pintype "passive"))
      (node (ref "D2") (pin "C") (pinfunction "C_C") (pintype "passive"))
      (node (ref "D3") (pin "A") (pinfunction "A_A") (pintype "passive"))
    )
    (net (code "52") (name "Net-(C10-Pad2)") (class "Default")
      (node (ref "C10") (pin "2") (pinfunction "2_2") (pintype "passive"))
      (node (ref "D1") (pin "A") (pinfunction "A_A") (pintype "passive"))
      (node (ref "L1") (pin "2") (pinfunction "2_2") (pintype "passive"))
      (node (ref "Q1") (pin "3") (pinfunction "3_3") (pintype "passive"))
    )
    (net (code "53") (name "Net-(C11-Pad1)") (class "Default")
      (node (ref "C11") (pin "1") (pinfunction "1_1") (pintype "passive"))
      (node (ref "U$1") (pin "18") (pinfunction "18_18") (pintype "bidirectional"))
    )
    (net (code "54") (name "Net-(CR2032-+-Pad+$1)") (class "Default")
      (node (ref "CR2032") (pin "+$1") (pinfunction "+_+$1") (pintype "passive"))
      (node (ref "CR2032") (pin "+$2") (pinfunction "+_+$2") (pintype "passive"))
      (node (ref "LSP1") (pin "MP") (pinfunction "MP_MP") (pintype "passive"))
    )
    (net (code "55") (name "Net-(D4-PadC)") (class "Default")
      (node (ref "D4") (pin "C") (pinfunction "C_C") (pintype "passive"))
      (node (ref "R6") (pin "1") (pinfunction "1_1") (pintype "passive"))
    )
    (net (code "56") (name "Net-(IC1-PROG)") (class "Default")
      (node (ref "IC1") (pin "5") (pinfunction "PROG_5") (pintype "input"))
      (node (ref "R7") (pin "1") (pinfunction "1_1") (pintype "passive"))
      (node (ref "RATE1") (pin "2") (pinfunction "2_2") (pintype "passive"))
      (node (ref "RATE2") (pin "2") (pinfunction "2_2") (pintype "passive"))
    )
    (net (code "57") (name "Net-(IC1-STAT)") (class "Default")
      (node (ref "IC1") (pin "1") (pinfunction "STAT_1") (pintype "output"))
      (node (ref "R6") (pin "2") (pinfunction "2_2") (pintype "passive"))
    )
    (net (code "58") (name "Net-(J1-CC1)") (class "Default")
      (node (ref "J1") (pin "A5") (pinfunction "CC1_A5") (pintype "passive"))
      (node (ref "R16") (pin "2") (pinfunction "2_2") (pintype "passive"))
    )
    (net (code "59") (name "Net-(J1-CC2)") (class "Default")
      (node (ref "J1") (pin "B5") (pinfunction "CC2_B5") (pintype "passive"))
      (node (ref "R15") (pin "2") (pinfunction "2_2") (pintype "passive"))
    )
    (net (code "60") (name "Net-(J1-D1+)") (class "Default")
      (node (ref "J1") (pin "A6") (pinfunction "D1+_A6") (pintype "passive"))
      (node (ref "J1") (pin "B6") (pinfunction "D2+_B6") (pintype "passive"))
      (node (ref "R18") (pin "2") (pinfunction "2_2") (pintype "passive"))
    )
    (net (code "61") (name "Net-(J1-D1-)") (class "Default")
      (node (ref "J1") (pin "A7") (pinfunction "D1-_A7") (pintype "passive"))
      (node (ref "J1") (pin "B7") (pinfunction "D2-_B7") (pintype "passive"))
      (node (ref "R17") (pin "2") (pinfunction "2_2") (pintype "passive"))
    )
    (net (code "62") (name "Net-(LED2-DO)") (class "Default")
      (node (ref "LED2") (pin "2-DOUT") (pinfunction "DO_2-DOUT") (pintype "output"))
      (node (ref "LED3") (pin "4-DIN") (pinfunction "DI_4-DIN") (pintype "input"))
    )
    (net (code "63") (name "Net-(LED3-DO)") (class "Default")
      (node (ref "LED3") (pin "2-DOUT") (pinfunction "DO_2-DOUT") (pintype "output"))
      (node (ref "LED4") (pin "4-DIN") (pinfunction "DI_4-DIN") (pintype "input"))
    )
    (net (code "64") (name "Net-(LED4-DO)") (class "Default")
      (node (ref "LED4") (pin "2-DOUT") (pinfunction "DO_2-DOUT") (pintype "output"))
      (node (ref "LED5") (pin "4-DIN") (pinfunction "DI_4-DIN") (pintype "input"))
    )
    (net (code "65") (name "Net-(Q1-Pad1)") (class "Default")
      (node (ref "Q1") (pin "1") (pinfunction "1_1") (pintype "passive"))
      (node (ref "R1") (pin "1") (pinfunction "1_1") (pintype "passive"))
      (node (ref "U$1") (pin "2") (pinfunction "2_2") (pintype "bidirectional"))
    )
    (net (code "66") (name "Net-(Q1-Pad2)") (class "Default")
      (node (ref "Q1") (pin "2") (pinfunction "2_2") (pintype "passive"))
      (node (ref "R2") (pin "1") (pinfunction "1_1") (pintype "passive"))
      (node (ref "U$1") (pin "3") (pinfunction "3_3") (pintype "bidirectional"))
    )
    (net (code "67") (name "Net-(Q2-S)") (class "Default")
      (node (ref "C14") (pin "1") (pinfunction "1_1") (pintype "passive"))
      (node (ref "D5") (pin "C") (pinfunction "C_C") (pintype "passive"))
      (node (ref "Q2") (pin "2") (pinfunction "S_2") (pintype "passive"))
      (node (ref "U2") (pin "1") (pinfunction "IN_1") (pintype "power_in"))
      (node (ref "U2") (pin "3") (pinfunction "EN_3") (pintype "input"))
    )
    (net (code "68") (name "Net-(R11-Pad1)") (class "Default")
      (node (ref "R11") (pin "1") (pinfunction "1_1") (pintype "passive"))
      (node (ref "RATE1") (pin "1") (pinfunction "1_1") (pintype "passive"))
    )
    (net (code "69") (name "Net-(R12-Pad1)") (class "Default")
      (node (ref "R12") (pin "1") (pinfunction "1_1") (pintype "passive"))
      (node (ref "RATE2") (pin "1") (pinfunction "1_1") (pintype "passive"))
    )
    (net (code "70") (name "Net-(U2-OUT)") (class "Default")
      (node (ref "LSP3") (pin "MP") (pinfunction "MP_MP") (pintype "passive"))
      (node (ref "U2") (pin "5") (pinfunction "OUT_5") (pintype "power_in"))
    )
    (net (code "71") (name "P8") (class "Default")
      (node (ref "R3") (pin "2") (pinfunction "2_2") (pintype "passive"))
      (node (ref "R4") (pin "2") (pinfunction "2_2") (pintype "passive"))
      (node (ref "U$1") (pin "8") (pinfunction "8_8") (pintype "bidirectional"))
    )
    (net (code "72") (name "V+") (class "Default")
      (node (ref "C16") (pin "1") (pinfunction "1_1") (pintype "passive"))
      (node (ref "C22") (pin "1") (pinfunction "1_1") (pintype "passive"))
      (node (ref "LED2") (pin "1-VDD") (pinfunction "VDD_1-VDD") (pintype "power_in"))
      (node (ref "LED3") (pin "1-VDD") (pinfunction "VDD_1-VDD") (pintype "power_in"))
      (node (ref "LED4") (pin "1-VDD") (pinfunction "VDD_1-VDD") (pintype "power_in"))
      (node (ref "LED5") (pin "1-VDD") (pinfunction "VDD_1-VDD") (pintype "power_in"))
      (node (ref "Q3") (pin "3") (pinfunction "D_3") (pintype "passive"))
    )
    (net (code "73") (name "unconnected-(J1-SBU1-PadA8)") (class "Default")
      (node (ref "J1") (pin "A8") (pinfunction "SBU1_A8") (pintype "passive"))
    )
    (net (code "74") (name "unconnected-(J1-SBU2-PadB8)") (class "Default")
      (node (ref "J1") (pin "B8") (pinfunction "SBU2_B8") (pintype "passive"))
    )
    (net (code "75") (name "unconnected-(LED5-DO-Pad2-DOUT)") (class "Default")
      (node (ref "LED5") (pin "2-DOUT") (pinfunction "DO_2-DOUT") (pintype "output"))
    )
    (net (code "76") (name "unconnected-(LSP4-PadMP)") (class "Default")
      (node (ref "LSP4") (pin "MP") (pinfunction "MP_MP") (pintype "passive"))
    )
    (net (code "77") (name "unconnected-(U$1-Pad1)") (class "Default")
      (node (ref "U$1") (pin "1") (pinfunction "1_1") (pintype "bidirectional"))
    )
    (net (code "78") (name "unconnected-(U$1-Pad6)") (class "Default")
      (node (ref "U$1") (pin "6") (pinfunction "6_6") (pintype "bidirectional"))
    )
    (net (code "79") (name "unconnected-(U$1-Pad7)") (class "Default")
      (node (ref "U$1") (pin "7") (pinfunction "7_7") (pintype "bidirectional"))
    )
    (net (code "80") (name "unconnected-(U2-P4-Pad4)") (class "Default")
      (node (ref "U2") (pin "4") (pinfunction "P4_4") (pintype "bidirectional"))
    )
  )
)
